# Variable_Output_1.net
KiCad netlist of a schematic drawn in Altium Designer
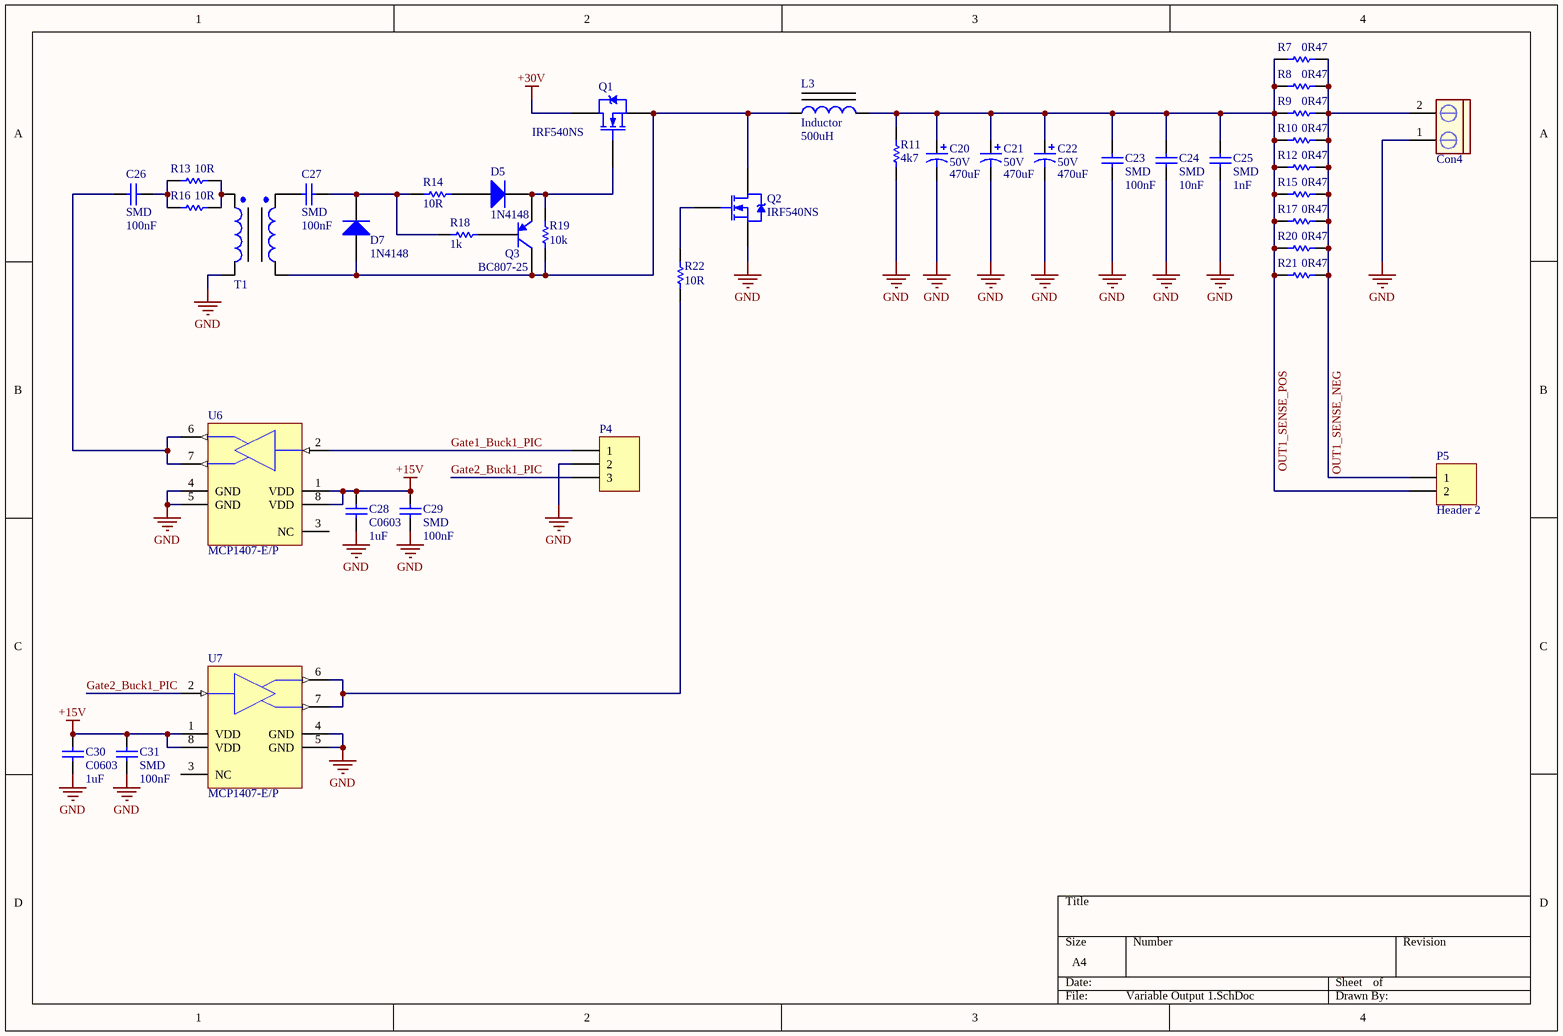
[diagram p0: Variable Output 1.SchDoc]

(export (version "E")
  (design (tool "Eeschema 10.0.6"))
  (components
    (comp (ref "C20")
      (value "50V")
      (footprint "CAPPR5-10X20")
      (description "Aluminum Electrolytic Capacitor, Radial Style with Long Leads: 470uF, 50V")
      (fields (field (name "ALTIUM_VALUE") "470uF") (field (name "PUBLISHER") "Altium Limited"))
      (libsource (lib "Vishay Roederstein Electrolytic Radial-Lead Capacitor") (part "EKB00DE347H00"))
    )
    (comp (ref "C21")
      (value "50V")
      (footprint "CAPPR5-10X20")
      (description "Aluminum Electrolytic Capacitor, Radial Style with Long Leads: 470uF, 50V")
      (fields (field (name "ALTIUM_VALUE") "470uF") (field (name "PUBLISHER") "Altium Limited"))
      (libsource (lib "Vishay Roederstein Electrolytic Radial-Lead Capacitor") (part "EKB00DE347H00"))
    )
    (comp (ref "C22")
      (value "50V")
      (footprint "CAPPR5-10X20")
      (description "Aluminum Electrolytic Capacitor, Radial Style with Long Leads: 470uF, 50V")
      (fields (field (name "ALTIUM_VALUE") "470uF") (field (name "PUBLISHER") "Altium Limited"))
      (libsource (lib "Vishay Roederstein Electrolytic Radial-Lead Capacitor") (part "EKB00DE347H00"))
    )
    (comp (ref "C23")
      (value "SMD")
      (footprint "1206")
      (description "Ceramic Chip Capacitor - Standard")
      (fields (field (name "ALTIUM_VALUE") "100nF") (field (name "PUBLISHER") "Altium Limited"))
      (libsource (lib "KEMET Chip Capacitor") (part "C1206"))
    )
    (comp (ref "C24")
      (value "SMD")
      (footprint "1206")
      (description "Ceramic Chip Capacitor - Standard")
      (fields (field (name "ALTIUM_VALUE") "10nF") (field (name "PUBLISHER") "Altium Limited"))
      (libsource (lib "KEMET Chip Capacitor") (part "C1206"))
    )
    (comp (ref "C25")
      (value "SMD")
      (footprint "1206")
      (description "Ceramic Chip Capacitor - Standard")
      (fields (field (name "ALTIUM_VALUE") "1nF") (field (name "PUBLISHER") "Altium Limited"))
      (libsource (lib "KEMET Chip Capacitor") (part "C1206"))
    )
    (comp (ref "C26")
      (value "SMD")
      (footprint "1206")
      (description "Ceramic Chip Capacitor - Standard")
      (fields (field (name "ALTIUM_VALUE") "100nF") (field (name "PUBLISHER") "Altium Limited"))
      (libsource (lib "KEMET Chip Capacitor") (part "C1206"))
    )
    (comp (ref "C27")
      (value "SMD")
      (footprint "1206")
      (description "Ceramic Chip Capacitor - Standard")
      (fields (field (name "ALTIUM_VALUE") "100nF") (field (name "PUBLISHER") "Altium Limited"))
      (libsource (lib "KEMET Chip Capacitor") (part "C1206"))
    )
    (comp (ref "C28")
      (value "C0603")
      (footprint "0603")
      (description "C1608X7R1C105K X7R")
      (fields (field (name "ALTIUM_VALUE") "1uF") (field (name "PUBLISHER") "Altium Limited"))
      (libsource (lib "KEMET Chip Capacitor") (part "C0603"))
    )
    (comp (ref "C29")
      (value "SMD")
      (footprint "1206")
      (description "Ceramic Chip Capacitor - Standard")
      (fields (field (name "ALTIUM_VALUE") "100nF") (field (name "PUBLISHER") "Altium Limited"))
      (libsource (lib "KEMET Chip Capacitor") (part "C1206"))
    )
    (comp (ref "C30")
      (value "C0603")
      (footprint "0603")
      (description "C1608X7R1C105K X7R")
      (fields (field (name "ALTIUM_VALUE") "1uF") (field (name "PUBLISHER") "Altium Limited"))
      (libsource (lib "KEMET Chip Capacitor") (part "C0603"))
    )
    (comp (ref "C31")
      (value "SMD")
      (footprint "1206")
      (description "Ceramic Chip Capacitor - Standard")
      (fields (field (name "ALTIUM_VALUE") "100nF") (field (name "PUBLISHER") "Altium Limited"))
      (libsource (lib "KEMET Chip Capacitor") (part "C1206"))
    )
    (comp (ref "Con4")
      (value "Salida Buck")
      (footprint "My_CN2")
      (description "Connector blue screw")
      (libsource (lib "Mylib") (part "CON2 pin blue"))
    )
    (comp (ref "D5")
      (value "1N4148")
      (footprint "Philips Discrete Diode - Switching:SOD80C")
      (description "High Conductance Fast Diode")
      (fields (field (name "PUBLISHER") "Altium Limited"))
      (libsource (lib "FSC Discrete Diode") (part "1N4148"))
    )
    (comp (ref "D7")
      (value "1N4148")
      (footprint "Philips Discrete Diode - Switching:SOD80C")
      (description "High Conductance Fast Diode")
      (fields (field (name "PUBLISHER") "Altium Limited"))
      (libsource (lib "FSC Discrete Diode") (part "1N4148"))
    )
    (comp (ref "L3")
      (value "Inductor")
      (footprint "R33x19x11 Toroid Vertical")
      (description "Generic Inductor")
      (fields (field (name "ALTIUM_VALUE") "500uH"))
      (libsource (lib "NXT - Inductors") (part "Generic Inductor"))
    )
    (comp (ref "P4")
      (value "Header 3")
      (footprint "My_1X03")
      (description "Header, 3-Pin")
      (fields (field (name "PUBLISHER") "Altium Limited"))
      (libsource (lib "Mylib") (part "Header 3"))
    )
    (comp (ref "P5")
      (value "Header 2")
      (footprint "HDR1X2")
      (description "Header, 2-Pin")
      (fields (field (name "PUBLISHER") "Altium Limited"))
      (libsource (lib "Miscellaneous Connectors") (part "Header 2"))
    )
    (comp (ref "Q1")
      (value "IRF540NS")
      (footprint "D2PAK_N")
      (description "HEXFET Power MOSFET")
      (fields (field (name "PUBLISHER") "Altium Limited"))
      (libsource (lib "IR Discrete MOSFET - Power") (part "IRF540NS"))
    )
    (comp (ref "Q2")
      (value "IRF540NS")
      (footprint "D2PAK_N")
      (description "HEXFET Power MOSFET")
      (fields (field (name "PUBLISHER") "Altium Limited"))
      (libsource (lib "IR Discrete MOSFET - Power") (part "IRF540NS"))
    )
    (comp (ref "Q3")
      (value "BC807-25")
      (footprint "SOT-23A_N")
      (description "PNP General Purpose Amplifier")
      (fields (field (name "PUBLISHER") "Altium Limited"))
      (libsource (lib "FSC Discrete BJT") (part "BC807-25"))
    )
    (comp (ref "R7")
      (value "0R47")
      (footprint "AXIAL-0.3")
      (description "Resistor")
      (fields (field (name "Comment") "Carbon") (field (name "PUBLISHER") "Altium Limited"))
      (libsource (lib "Miscellaneous Devices") (part "Res1"))
    )
    (comp (ref "R8")
      (value "0R47")
      (footprint "AXIAL-0.3")
      (description "Resistor")
      (fields (field (name "Comment") "Carbon") (field (name "PUBLISHER") "Altium Limited"))
      (libsource (lib "Miscellaneous Devices") (part "Res1"))
    )
    (comp (ref "R9")
      (value "0R47")
      (footprint "AXIAL-0.3")
      (description "Resistor")
      (fields (field (name "Comment") "Carbon") (field (name "PUBLISHER") "Altium Limited"))
      (libsource (lib "Miscellaneous Devices") (part "Res1"))
    )
    (comp (ref "R10")
      (value "0R47")
      (footprint "AXIAL-0.3")
      (description "Resistor")
      (fields (field (name "Comment") "Carbon") (field (name "PUBLISHER") "Altium Limited"))
      (libsource (lib "Miscellaneous Devices") (part "Res1"))
    )
    (comp (ref "R11")
      (value "4k7")
      (footprint "8RB-1206")
      (fields (field (name "Comment") "SMD") (field (name "PUBLISHER") "Altium Limited"))
      (libsource (lib "Panasonic Resistor") (part "ERJ8BQ"))
    )
    (comp (ref "R12")
      (value "0R47")
      (footprint "AXIAL-0.3")
      (description "Resistor")
      (fields (field (name "Comment") "Carbon") (field (name "PUBLISHER") "Altium Limited"))
      (libsource (lib "Miscellaneous Devices") (part "Res1"))
    )
    (comp (ref "R13")
      (value "10R")
      (footprint "8RB-1206")
      (fields (field (name "Comment") "SMD 1206") (field (name "PUBLISHER") "Altium Limited"))
      (libsource (lib "Panasonic Resistor") (part "ERJ8BQ"))
    )
    (comp (ref "R14")
      (value "10R")
      (footprint "8RB-1206")
      (fields (field (name "Comment") "SMD 1206") (field (name "PUBLISHER") "Altium Limited"))
      (libsource (lib "Panasonic Resistor") (part "ERJ8BQ"))
    )
    (comp (ref "R15")
      (value "0R47")
      (footprint "AXIAL-0.3")
      (description "Resistor")
      (fields (field (name "Comment") "Carbon") (field (name "PUBLISHER") "Altium Limited"))
      (libsource (lib "Miscellaneous Devices") (part "Res1"))
    )
    (comp (ref "R16")
      (value "10R")
      (footprint "8RB-1206")
      (fields (field (name "Comment") "SMD 1206") (field (name "PUBLISHER") "Altium Limited"))
      (libsource (lib "Panasonic Resistor") (part "ERJ8BQ"))
    )
    (comp (ref "R17")
      (value "0R47")
      (footprint "AXIAL-0.3")
      (description "Resistor")
      (fields (field (name "Comment") "Carbon") (field (name "PUBLISHER") "Altium Limited"))
      (libsource (lib "Miscellaneous Devices") (part "Res1"))
    )
    (comp (ref "R18")
      (value "1k")
      (footprint "8RB-1206")
      (fields (field (name "Comment") "SMD") (field (name "PUBLISHER") "Altium Limited"))
      (libsource (lib "Panasonic Resistor") (part "ERJ8BQ"))
    )
    (comp (ref "R19")
      (value "10k")
      (footprint "8RB-1206")
      (fields (field (name "Comment") "SMD") (field (name "PUBLISHER") "Altium Limited"))
      (libsource (lib "Panasonic Resistor") (part "ERJ8BQ"))
    )
    (comp (ref "R20")
      (value "0R47")
      (footprint "AXIAL-0.3")
      (description "Resistor")
      (fields (field (name "Comment") "Carbon") (field (name "PUBLISHER") "Altium Limited"))
      (libsource (lib "Miscellaneous Devices") (part "Res1"))
    )
    (comp (ref "R21")
      (value "0R47")
      (footprint "AXIAL-0.3")
      (description "Resistor")
      (fields (field (name "Comment") "Carbon") (field (name "PUBLISHER") "Altium Limited"))
      (libsource (lib "Miscellaneous Devices") (part "Res1"))
    )
    (comp (ref "R22")
      (value "10R")
      (footprint "8RB-1206")
      (fields (field (name "Comment") "SMD 1206") (field (name "PUBLISHER") "Altium Limited"))
      (libsource (lib "Panasonic Resistor") (part "ERJ8BQ"))
    )
    (comp (ref "T1")
      (value "Gate Driver Transformer 15mm Toroidal")
      (footprint "Gate Driver Transformer 15mm Toroidal")
      (libsource (lib "NXT - Inductors") (part "Gate Driver Transformer 15mm Toroidal"))
    )
    (comp (ref "U6")
      (value "MCP1407-E/P")
      (footprint "PDIP300-P8")
      (description "6A High-Speed Power MOSFET Drivers, Non Inverting, Extended Temperature")
      (fields (field (name "PUBLISHER") "Altium Limited"))
      (libsource (lib "Microchip Power Mgt MOSFET Driver") (part "MCP1407-E/P"))
    )
    (comp (ref "U7")
      (value "MCP1407-E/P")
      (footprint "PDIP300-P8")
      (description "6A High-Speed Power MOSFET Drivers, Non Inverting, Extended Temperature")
      (fields (field (name "PUBLISHER") "Altium Limited"))
      (libsource (lib "") (part "MCP1407-E/P_1"))
    )
  )
  (nets
    (net (code "1") (name "+15V") (class "Default")
      (node (ref "C28") (pin "2") (pinfunction "2_2") (pintype "passive"))
      (node (ref "C29") (pin "2") (pinfunction "2_2") (pintype "passive"))
      (node (ref "C30") (pin "2") (pinfunction "2_2") (pintype "passive"))
      (node (ref "C31") (pin "2") (pinfunction "2_2") (pintype "passive"))
      (node (ref "U6") (pin "1") (pinfunction "VDD_1") (pintype "power_in"))
      (node (ref "U6") (pin "8") (pinfunction "VDD_8") (pintype "power_in"))
      (node (ref "U7") (pin "1") (pinfunction "VDD_1") (pintype "power_in"))
      (node (ref "U7") (pin "8") (pinfunction "VDD_8") (pintype "power_in"))
    )
    (net (code "2") (name "+30V") (class "Default")
      (node (ref "Q1") (pin "2") (pinfunction "D_2") (pintype "passive"))
    )
    (net (code "3") (name "/Gate1_Buck1_PIC") (class "Default")
      (node (ref "P4") (pin "1") (pinfunction "1_1") (pintype "passive"))
      (node (ref "U6") (pin "2") (pinfunction "IN_2") (pintype "input"))
    )
    (net (code "4") (name "/Gate2_Buck1_PIC") (class "Default")
      (node (ref "P4") (pin "3") (pinfunction "3_3") (pintype "passive"))
      (node (ref "U7") (pin "2") (pinfunction "IN_2") (pintype "input"))
    )
    (net (code "5") (name "/OUT1_SENSE_NEG") (class "Default")
      (node (ref "Con4") (pin "2") (pinfunction "2_2") (pintype "passive"))
      (node (ref "P5") (pin "1") (pinfunction "1_1") (pintype "passive"))
      (node (ref "R10") (pin "2") (pinfunction "2_2") (pintype "passive"))
      (node (ref "R12") (pin "2") (pinfunction "2_2") (pintype "passive"))
      (node (ref "R15") (pin "2") (pinfunction "2_2") (pintype "passive"))
      (node (ref "R17") (pin "2") (pinfunction "2_2") (pintype "passive"))
      (node (ref "R20") (pin "2") (pinfunction "2_2") (pintype "passive"))
      (node (ref "R21") (pin "2") (pinfunction "2_2") (pintype "passive"))
      (node (ref "R7") (pin "2") (pinfunction "2_2") (pintype "passive"))
      (node (ref "R8") (pin "2") (pinfunction "2_2") (pintype "passive"))
      (node (ref "R9") (pin "2") (pinfunction "2_2") (pintype "passive"))
    )
    (net (code "6") (name "/OUT1_SENSE_POS") (class "Default")
      (node (ref "C20") (pin "1") (pinfunction "1_1") (pintype "passive"))
      (node (ref "C21") (pin "1") (pinfunction "1_1") (pintype "passive"))
      (node (ref "C22") (pin "1") (pinfunction "1_1") (pintype "passive"))
      (node (ref "C23") (pin "2") (pinfunction "2_2") (pintype "passive"))
      (node (ref "C24") (pin "2") (pinfunction "2_2") (pintype "passive"))
      (node (ref "C25") (pin "2") (pinfunction "2_2") (pintype "passive"))
      (node (ref "L3") (pin "2") (pinfunction "2_2") (pintype "passive"))
      (node (ref "P5") (pin "2") (pinfunction "2_2") (pintype "passive"))
      (node (ref "R10") (pin "1") (pinfunction "1_1") (pintype "passive"))
      (node (ref "R11") (pin "2") (pinfunction "2_2") (pintype "passive"))
      (node (ref "R12") (pin "1") (pinfunction "1_1") (pintype "passive"))
      (node (ref "R15") (pin "1") (pinfunction "1_1") (pintype "passive"))
      (node (ref "R17") (pin "1") (pinfunction "1_1") (pintype "passive"))
      (node (ref "R20") (pin "1") (pinfunction "1_1") (pintype "passive"))
      (node (ref "R21") (pin "1") (pinfunction "1_1") (pintype "passive"))
      (node (ref "R7") (pin "1") (pinfunction "1_1") (pintype "passive"))
      (node (ref "R8") (pin "1") (pinfunction "1_1") (pintype "passive"))
      (node (ref "R9") (pin "1") (pinfunction "1_1") (pintype "passive"))
    )
    (net (code "7") (name "GND") (class "Default")
      (node (ref "C20") (pin "2") (pinfunction "2_2") (pintype "passive"))
      (node (ref "C21") (pin "2") (pinfunction "2_2") (pintype "passive"))
      (node (ref "C22") (pin "2") (pinfunction "2_2") (pintype "passive"))
      (node (ref "C23") (pin "1") (pinfunction "1_1") (pintype "passive"))
      (node (ref "C24") (pin "1") (pinfunction "1_1") (pintype "passive"))
      (node (ref "C25") (pin "1") (pinfunction "1_1") (pintype "passive"))
      (node (ref "C28") (pin "1") (pinfunction "1_1") (pintype "passive"))
      (node (ref "C29") (pin "1") (pinfunction "1_1") (pintype "passive"))
      (node (ref "C30") (pin "1") (pinfunction "1_1") (pintype "passive"))
      (node (ref "C31") (pin "1") (pinfunction "1_1") (pintype "passive"))
      (node (ref "Con4") (pin "1") (pinfunction "1_1") (pintype "passive"))
      (node (ref "P4") (pin "2") (pinfunction "2_2") (pintype "passive"))
      (node (ref "Q2") (pin "3") (pinfunction "S_3") (pintype "passive"))
      (node (ref "R11") (pin "1") (pinfunction "1_1") (pintype "passive"))
      (node (ref "T1") (pin "2") (pinfunction "2_2") (pintype "passive"))
      (node (ref "U6") (pin "4") (pinfunction "GND_4") (pintype "power_in"))
      (node (ref "U6") (pin "5") (pinfunction "GND_5") (pintype "power_in"))
      (node (ref "U7") (pin "4") (pinfunction "GND_4") (pintype "power_in"))
      (node (ref "U7") (pin "5") (pinfunction "GND_5") (pintype "power_in"))
    )
    (net (code "8") (name "Net-(C26-Pad1)") (class "Default")
      (node (ref "C26") (pin "1") (pinfunction "1_1") (pintype "passive"))
      (node (ref "U6") (pin "6") (pinfunction "OUT_6") (pintype "output"))
      (node (ref "U6") (pin "7") (pinfunction "OUT_7") (pintype "output"))
    )
    (net (code "9") (name "Net-(C26-Pad2)") (class "Default")
      (node (ref "C26") (pin "2") (pinfunction "2_2") (pintype "passive"))
      (node (ref "R13") (pin "1") (pinfunction "1_1") (pintype "passive"))
      (node (ref "R16") (pin "1") (pinfunction "1_1") (pintype "passive"))
    )
    (net (code "10") (name "Net-(C27-Pad1)") (class "Default")
      (node (ref "C27") (pin "1") (pinfunction "1_1") (pintype "passive"))
      (node (ref "T1") (pin "3") (pinfunction "3_3") (pintype "passive"))
    )
    (net (code "11") (name "Net-(D5-A)") (class "Default")
      (node (ref "D5") (pin "1") (pinfunction "A_1") (pintype "passive"))
      (node (ref "R14") (pin "2") (pinfunction "2_2") (pintype "passive"))
    )
    (net (code "12") (name "Net-(D5-K)") (class "Default")
      (node (ref "D5") (pin "2") (pinfunction "K_2") (pintype "passive"))
      (node (ref "Q1") (pin "1") (pinfunction "G_1") (pintype "passive"))
      (node (ref "Q3") (pin "2") (pinfunction "E_2") (pintype "passive"))
      (node (ref "R19") (pin "2") (pinfunction "2_2") (pintype "passive"))
    )
    (net (code "13") (name "Net-(D7-A)") (class "Default")
      (node (ref "D7") (pin "1") (pinfunction "A_1") (pintype "passive"))
      (node (ref "L3") (pin "1") (pinfunction "1_1") (pintype "passive"))
      (node (ref "Q1") (pin "3") (pinfunction "S_3") (pintype "passive"))
      (node (ref "Q2") (pin "2") (pinfunction "D_2") (pintype "passive"))
      (node (ref "Q3") (pin "3") (pinfunction "C_3") (pintype "passive"))
      (node (ref "R19") (pin "1") (pinfunction "1_1") (pintype "passive"))
      (node (ref "T1") (pin "4") (pinfunction "4_4") (pintype "passive"))
    )
    (net (code "14") (name "Net-(D7-K)") (class "Default")
      (node (ref "C27") (pin "2") (pinfunction "2_2") (pintype "passive"))
      (node (ref "D7") (pin "2") (pinfunction "K_2") (pintype "passive"))
      (node (ref "R14") (pin "1") (pinfunction "1_1") (pintype "passive"))
      (node (ref "R18") (pin "2") (pinfunction "2_2") (pintype "passive"))
    )
    (net (code "15") (name "Net-(Q2-G)") (class "Default")
      (node (ref "Q2") (pin "1") (pinfunction "G_1") (pintype "passive"))
      (node (ref "R22") (pin "1") (pinfunction "1_1") (pintype "passive"))
    )
    (net (code "16") (name "Net-(Q3-B)") (class "Default")
      (node (ref "Q3") (pin "1") (pinfunction "B_1") (pintype "passive"))
      (node (ref "R18") (pin "1") (pinfunction "1_1") (pintype "passive"))
    )
    (net (code "17") (name "Net-(R13-Pad2)") (class "Default")
      (node (ref "R13") (pin "2") (pinfunction "2_2") (pintype "passive"))
      (node (ref "R16") (pin "2") (pinfunction "2_2") (pintype "passive"))
      (node (ref "T1") (pin "1") (pinfunction "1_1") (pintype "passive"))
    )
    (net (code "18") (name "Net-(R22-Pad2)") (class "Default")
      (node (ref "R22") (pin "2") (pinfunction "2_2") (pintype "passive"))
      (node (ref "U7") (pin "6") (pinfunction "OUT_6") (pintype "output"))
      (node (ref "U7") (pin "7") (pinfunction "OUT_7") (pintype "output"))
    )
    (net (code "19") (name "unconnected-(U6-NC-Pad3)") (class "Default")
      (node (ref "U6") (pin "3") (pinfunction "NC_3") (pintype "passive"))
    )
    (net (code "20") (name "unconnected-(U7-NC-Pad3)") (class "Default")
      (node (ref "U7") (pin "3") (pinfunction "NC_3") (pintype "passive"))
    )
  )
)
